# Quad_VCA_CTRL_v1.net
KiCad netlist of a schematic drawn in EAGLE
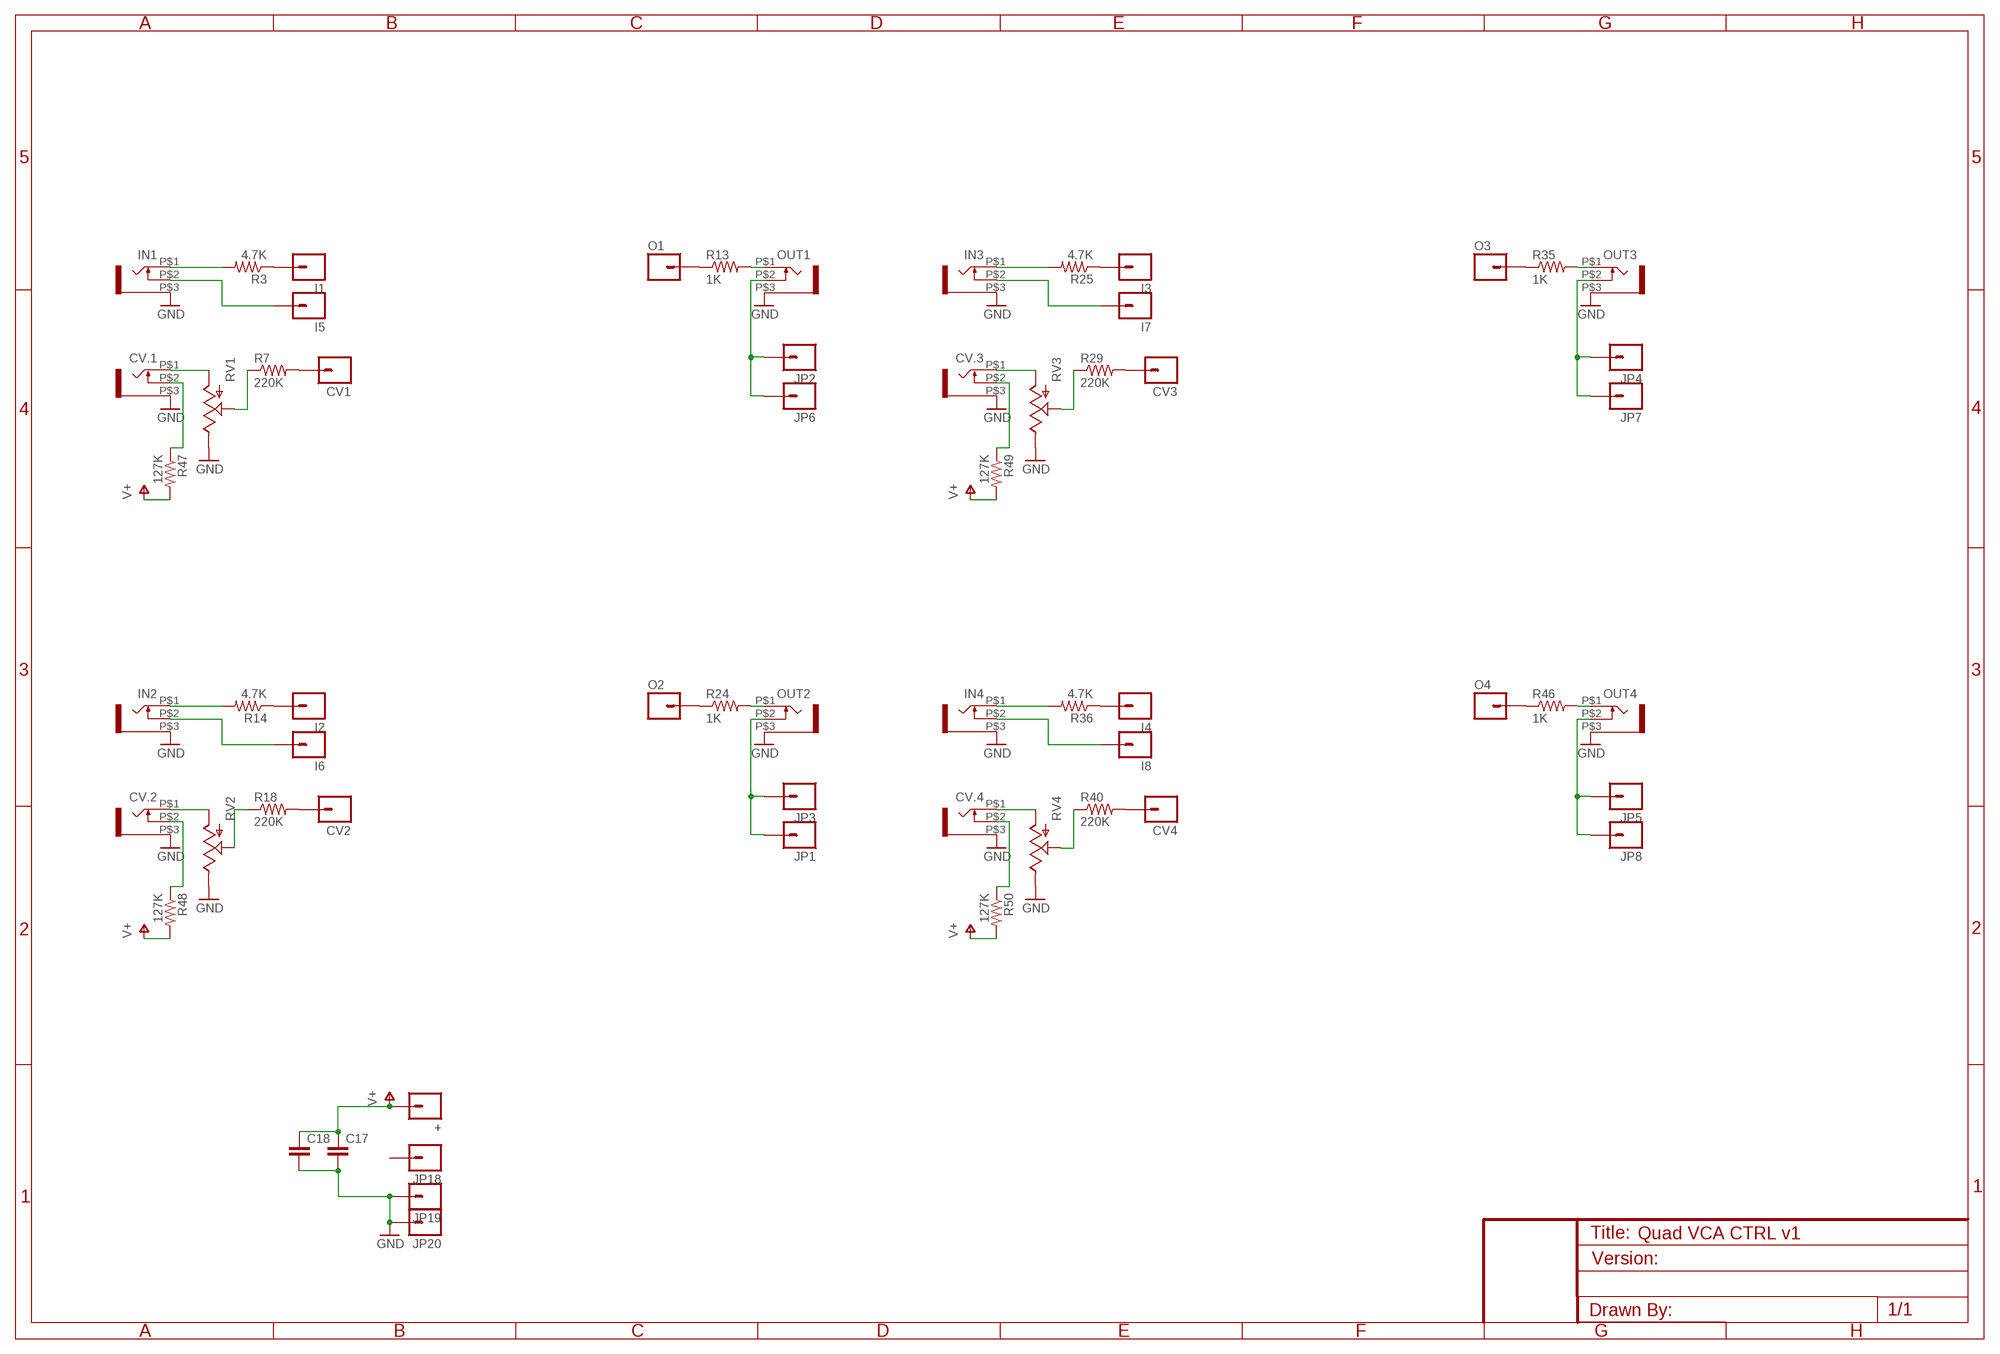
[diagram p0: schematic, sheet 1]

(export (version "E")
  (design (tool "Eeschema 10.0.6"))
  (components
    (comp (ref "+")
      (value "M01PTH")
      (footprint "eagle-import:1X01")
      (libsource (lib "eagle-import") (part "M01PTH"))
    )
    (comp (ref "C17")
      (value "CAP0805")
      (footprint "eagle-import:0805")
      (libsource (lib "eagle-import") (part "CAP0805"))
    )
    (comp (ref "C18")
      (value "CAP0805")
      (footprint "eagle-import:0805")
      (libsource (lib "eagle-import") (part "CAP0805"))
    )
    (comp (ref "CV.1")
      (value "WQP-PJ301M-12_JACK")
      (footprint "eagle-import:WQP-PJ301M-12_JACK")
      (libsource (lib "eagle-import") (part "WQP-PJ301M-12_JACK"))
    )
    (comp (ref "CV.2")
      (value "WQP-PJ301M-12_JACK")
      (footprint "eagle-import:WQP-PJ301M-12_JACK")
      (libsource (lib "eagle-import") (part "WQP-PJ301M-12_JACK"))
    )
    (comp (ref "CV.3")
      (value "WQP-PJ301M-12_JACK")
      (footprint "eagle-import:WQP-PJ301M-12_JACK")
      (libsource (lib "eagle-import") (part "WQP-PJ301M-12_JACK"))
    )
    (comp (ref "CV.4")
      (value "WQP-PJ301M-12_JACK")
      (footprint "eagle-import:WQP-PJ301M-12_JACK")
      (libsource (lib "eagle-import") (part "WQP-PJ301M-12_JACK"))
    )
    (comp (ref "CV1")
      (value "M01PTH")
      (footprint "eagle-import:1X01")
      (libsource (lib "eagle-import") (part "M01PTH"))
    )
    (comp (ref "CV2")
      (value "M01PTH")
      (footprint "eagle-import:1X01")
      (libsource (lib "eagle-import") (part "M01PTH"))
    )
    (comp (ref "CV3")
      (value "M01PTH")
      (footprint "eagle-import:1X01")
      (libsource (lib "eagle-import") (part "M01PTH"))
    )
    (comp (ref "CV4")
      (value "M01PTH")
      (footprint "eagle-import:1X01")
      (libsource (lib "eagle-import") (part "M01PTH"))
    )
    (comp (ref "I1")
      (value "M01PTH")
      (footprint "eagle-import:1X01")
      (libsource (lib "eagle-import") (part "M01PTH"))
    )
    (comp (ref "I2")
      (value "M01PTH")
      (footprint "eagle-import:1X01")
      (libsource (lib "eagle-import") (part "M01PTH"))
    )
    (comp (ref "I3")
      (value "M01PTH")
      (footprint "eagle-import:1X01")
      (libsource (lib "eagle-import") (part "M01PTH"))
    )
    (comp (ref "I4")
      (value "M01PTH")
      (footprint "eagle-import:1X01")
      (libsource (lib "eagle-import") (part "M01PTH"))
    )
    (comp (ref "I5")
      (value "M01PTH")
      (footprint "eagle-import:1X01")
      (libsource (lib "eagle-import") (part "M01PTH"))
    )
    (comp (ref "I6")
      (value "M01PTH")
      (footprint "eagle-import:1X01")
      (libsource (lib "eagle-import") (part "M01PTH"))
    )
    (comp (ref "I7")
      (value "M01PTH")
      (footprint "eagle-import:1X01")
      (libsource (lib "eagle-import") (part "M01PTH"))
    )
    (comp (ref "I8")
      (value "M01PTH")
      (footprint "eagle-import:1X01")
      (libsource (lib "eagle-import") (part "M01PTH"))
    )
    (comp (ref "IN1")
      (value "WQP-PJ301M-12_JACK")
      (footprint "eagle-import:WQP-PJ301M-12_JACK")
      (libsource (lib "eagle-import") (part "WQP-PJ301M-12_JACK"))
    )
    (comp (ref "IN2")
      (value "WQP-PJ301M-12_JACK")
      (footprint "eagle-import:WQP-PJ301M-12_JACK")
      (libsource (lib "eagle-import") (part "WQP-PJ301M-12_JACK"))
    )
    (comp (ref "IN3")
      (value "WQP-PJ301M-12_JACK")
      (footprint "eagle-import:WQP-PJ301M-12_JACK")
      (libsource (lib "eagle-import") (part "WQP-PJ301M-12_JACK"))
    )
    (comp (ref "IN4")
      (value "WQP-PJ301M-12_JACK")
      (footprint "eagle-import:WQP-PJ301M-12_JACK")
      (libsource (lib "eagle-import") (part "WQP-PJ301M-12_JACK"))
    )
    (comp (ref "JP1")
      (value "M01PTH")
      (footprint "eagle-import:1X01")
      (libsource (lib "eagle-import") (part "M01PTH"))
    )
    (comp (ref "JP2")
      (value "M01PTH")
      (footprint "eagle-import:1X01")
      (libsource (lib "eagle-import") (part "M01PTH"))
    )
    (comp (ref "JP3")
      (value "M01PTH")
      (footprint "eagle-import:1X01")
      (libsource (lib "eagle-import") (part "M01PTH"))
    )
    (comp (ref "JP4")
      (value "M01PTH")
      (footprint "eagle-import:1X01")
      (libsource (lib "eagle-import") (part "M01PTH"))
    )
    (comp (ref "JP5")
      (value "M01PTH")
      (footprint "eagle-import:1X01")
      (libsource (lib "eagle-import") (part "M01PTH"))
    )
    (comp (ref "JP6")
      (value "M01PTH")
      (footprint "eagle-import:1X01")
      (libsource (lib "eagle-import") (part "M01PTH"))
    )
    (comp (ref "JP7")
      (value "M01PTH")
      (footprint "eagle-import:1X01")
      (libsource (lib "eagle-import") (part "M01PTH"))
    )
    (comp (ref "JP8")
      (value "M01PTH")
      (footprint "eagle-import:1X01")
      (libsource (lib "eagle-import") (part "M01PTH"))
    )
    (comp (ref "JP18")
      (value "M01PTH")
      (footprint "eagle-import:1X01")
      (libsource (lib "eagle-import") (part "M01PTH"))
    )
    (comp (ref "JP19")
      (value "M01PTH")
      (footprint "eagle-import:1X01")
      (libsource (lib "eagle-import") (part "M01PTH"))
    )
    (comp (ref "JP20")
      (value "M01PTH")
      (footprint "eagle-import:1X01")
      (libsource (lib "eagle-import") (part "M01PTH"))
    )
    (comp (ref "O1")
      (value "M01PTH")
      (footprint "eagle-import:1X01")
      (libsource (lib "eagle-import") (part "M01PTH"))
    )
    (comp (ref "O2")
      (value "M01PTH")
      (footprint "eagle-import:1X01")
      (libsource (lib "eagle-import") (part "M01PTH"))
    )
    (comp (ref "O3")
      (value "M01PTH")
      (footprint "eagle-import:1X01")
      (libsource (lib "eagle-import") (part "M01PTH"))
    )
    (comp (ref "O4")
      (value "M01PTH")
      (footprint "eagle-import:1X01")
      (libsource (lib "eagle-import") (part "M01PTH"))
    )
    (comp (ref "OUT1")
      (value "WQP-PJ301M-12_JACK")
      (footprint "eagle-import:WQP-PJ301M-12_JACK")
      (libsource (lib "eagle-import") (part "WQP-PJ301M-12_JACK"))
    )
    (comp (ref "OUT2")
      (value "WQP-PJ301M-12_JACK")
      (footprint "eagle-import:WQP-PJ301M-12_JACK")
      (libsource (lib "eagle-import") (part "WQP-PJ301M-12_JACK"))
    )
    (comp (ref "OUT3")
      (value "WQP-PJ301M-12_JACK")
      (footprint "eagle-import:WQP-PJ301M-12_JACK")
      (libsource (lib "eagle-import") (part "WQP-PJ301M-12_JACK"))
    )
    (comp (ref "OUT4")
      (value "WQP-PJ301M-12_JACK")
      (footprint "eagle-import:WQP-PJ301M-12_JACK")
      (libsource (lib "eagle-import") (part "WQP-PJ301M-12_JACK"))
    )
    (comp (ref "R3")
      (value "4.7K")
      (footprint "eagle-import:0805")
      (libsource (lib "eagle-import") (part "RESISTOR0805-RES"))
    )
    (comp (ref "R7")
      (value "220K")
      (footprint "eagle-import:0805")
      (libsource (lib "eagle-import") (part "RESISTOR0805-RES"))
    )
    (comp (ref "R13")
      (value "1K")
      (footprint "eagle-import:0805")
      (libsource (lib "eagle-import") (part "RESISTOR0805-RES"))
    )
    (comp (ref "R14")
      (value "4.7K")
      (footprint "eagle-import:0805")
      (libsource (lib "eagle-import") (part "RESISTOR0805-RES"))
    )
    (comp (ref "R18")
      (value "220K")
      (footprint "eagle-import:0805")
      (libsource (lib "eagle-import") (part "RESISTOR0805-RES"))
    )
    (comp (ref "R24")
      (value "1K")
      (footprint "eagle-import:0805")
      (libsource (lib "eagle-import") (part "RESISTOR0805-RES"))
    )
    (comp (ref "R25")
      (value "4.7K")
      (footprint "eagle-import:0805")
      (libsource (lib "eagle-import") (part "RESISTOR0805-RES"))
    )
    (comp (ref "R29")
      (value "220K")
      (footprint "eagle-import:0805")
      (libsource (lib "eagle-import") (part "RESISTOR0805-RES"))
    )
    (comp (ref "R35")
      (value "1K")
      (footprint "eagle-import:0805")
      (libsource (lib "eagle-import") (part "RESISTOR0805-RES"))
    )
    (comp (ref "R36")
      (value "4.7K")
      (footprint "eagle-import:0805")
      (libsource (lib "eagle-import") (part "RESISTOR0805-RES"))
    )
    (comp (ref "R40")
      (value "220K")
      (footprint "eagle-import:0805")
      (libsource (lib "eagle-import") (part "RESISTOR0805-RES"))
    )
    (comp (ref "R46")
      (value "1K")
      (footprint "eagle-import:0805")
      (libsource (lib "eagle-import") (part "RESISTOR0805-RES"))
    )
    (comp (ref "R47")
      (value "127K")
      (footprint "eagle-import:0805")
      (libsource (lib "eagle-import") (part "RESISTOR0805-RES"))
    )
    (comp (ref "R48")
      (value "127K")
      (footprint "eagle-import:0805")
      (libsource (lib "eagle-import") (part "RESISTOR0805-RES"))
    )
    (comp (ref "R49")
      (value "127K")
      (footprint "eagle-import:0805")
      (libsource (lib "eagle-import") (part "RESISTOR0805-RES"))
    )
    (comp (ref "R50")
      (value "127K")
      (footprint "eagle-import:0805")
      (libsource (lib "eagle-import") (part "RESISTOR0805-RES"))
    )
    (comp (ref "RV1")
      (value "POT")
      (footprint "eagle-import:ALPS_POT")
      (libsource (lib "eagle-import") (part "POT"))
    )
    (comp (ref "RV2")
      (value "POT")
      (footprint "eagle-import:ALPS_POT")
      (libsource (lib "eagle-import") (part "POT"))
    )
    (comp (ref "RV3")
      (value "POT")
      (footprint "eagle-import:ALPS_POT")
      (libsource (lib "eagle-import") (part "POT"))
    )
    (comp (ref "RV4")
      (value "POT")
      (footprint "eagle-import:ALPS_POT")
      (libsource (lib "eagle-import") (part "POT"))
    )
  )
  (nets
    (net (code "1") (name "GND") (class "Default")
      (node (ref "C17") (pin "2") (pinfunction "2_2") (pintype "passive"))
      (node (ref "C18") (pin "2") (pinfunction "2_2") (pintype "passive"))
      (node (ref "CV.1") (pin "P$3") (pinfunction "1_P$3") (pintype "passive"))
      (node (ref "CV.2") (pin "P$3") (pinfunction "1_P$3") (pintype "passive"))
      (node (ref "CV.3") (pin "P$3") (pinfunction "1_P$3") (pintype "passive"))
      (node (ref "CV.4") (pin "P$3") (pinfunction "1_P$3") (pintype "passive"))
      (node (ref "IN1") (pin "P$3") (pinfunction "1_P$3") (pintype "passive"))
      (node (ref "IN2") (pin "P$3") (pinfunction "1_P$3") (pintype "passive"))
      (node (ref "IN3") (pin "P$3") (pinfunction "1_P$3") (pintype "passive"))
      (node (ref "IN4") (pin "P$3") (pinfunction "1_P$3") (pintype "passive"))
      (node (ref "JP19") (pin "1") (pinfunction "1_1") (pintype "passive"))
      (node (ref "JP20") (pin "1") (pinfunction "1_1") (pintype "passive"))
      (node (ref "OUT1") (pin "P$3") (pinfunction "1_P$3") (pintype "passive"))
      (node (ref "OUT2") (pin "P$3") (pinfunction "1_P$3") (pintype "passive"))
      (node (ref "OUT3") (pin "P$3") (pinfunction "1_P$3") (pintype "passive"))
      (node (ref "OUT4") (pin "P$3") (pinfunction "1_P$3") (pintype "passive"))
      (node (ref "RV1") (pin "P$1") (pinfunction "E_P$1") (pintype "passive"))
      (node (ref "RV2") (pin "P$1") (pinfunction "E_P$1") (pintype "passive"))
      (node (ref "RV3") (pin "P$1") (pinfunction "E_P$1") (pintype "passive"))
      (node (ref "RV4") (pin "P$1") (pinfunction "E_P$1") (pintype "passive"))
    )
    (net (code "2") (name "Net-(CV.1-2)") (class "Default")
      (node (ref "CV.1") (pin "P$1") (pinfunction "2_P$1") (pintype "passive"))
      (node (ref "RV1") (pin "P$3") (pinfunction "A_P$3") (pintype "passive"))
    )
    (net (code "3") (name "Net-(CV.1-3)") (class "Default")
      (node (ref "CV.1") (pin "P$2") (pinfunction "3_P$2") (pintype "passive"))
      (node (ref "R47") (pin "1") (pinfunction "1_1") (pintype "passive"))
    )
    (net (code "4") (name "Net-(CV.2-2)") (class "Default")
      (node (ref "CV.2") (pin "P$1") (pinfunction "2_P$1") (pintype "passive"))
      (node (ref "RV2") (pin "P$3") (pinfunction "A_P$3") (pintype "passive"))
    )
    (net (code "5") (name "Net-(CV.2-3)") (class "Default")
      (node (ref "CV.2") (pin "P$2") (pinfunction "3_P$2") (pintype "passive"))
      (node (ref "R48") (pin "1") (pinfunction "1_1") (pintype "passive"))
    )
    (net (code "6") (name "Net-(CV.3-2)") (class "Default")
      (node (ref "CV.3") (pin "P$1") (pinfunction "2_P$1") (pintype "passive"))
      (node (ref "RV3") (pin "P$3") (pinfunction "A_P$3") (pintype "passive"))
    )
    (net (code "7") (name "Net-(CV.3-3)") (class "Default")
      (node (ref "CV.3") (pin "P$2") (pinfunction "3_P$2") (pintype "passive"))
      (node (ref "R49") (pin "1") (pinfunction "1_1") (pintype "passive"))
    )
    (net (code "8") (name "Net-(CV.4-2)") (class "Default")
      (node (ref "CV.4") (pin "P$1") (pinfunction "2_P$1") (pintype "passive"))
      (node (ref "RV4") (pin "P$3") (pinfunction "A_P$3") (pintype "passive"))
    )
    (net (code "9") (name "Net-(CV.4-3)") (class "Default")
      (node (ref "CV.4") (pin "P$2") (pinfunction "3_P$2") (pintype "passive"))
      (node (ref "R50") (pin "1") (pinfunction "1_1") (pintype "passive"))
    )
    (net (code "10") (name "Net-(CV1-Pad1)") (class "Default")
      (node (ref "CV1") (pin "1") (pinfunction "1_1") (pintype "passive"))
      (node (ref "R7") (pin "2") (pinfunction "2_2") (pintype "passive"))
    )
    (net (code "11") (name "Net-(CV2-Pad1)") (class "Default")
      (node (ref "CV2") (pin "1") (pinfunction "1_1") (pintype "passive"))
      (node (ref "R18") (pin "2") (pinfunction "2_2") (pintype "passive"))
    )
    (net (code "12") (name "Net-(CV3-Pad1)") (class "Default")
      (node (ref "CV3") (pin "1") (pinfunction "1_1") (pintype "passive"))
      (node (ref "R29") (pin "2") (pinfunction "2_2") (pintype "passive"))
    )
    (net (code "13") (name "Net-(CV4-Pad1)") (class "Default")
      (node (ref "CV4") (pin "1") (pinfunction "1_1") (pintype "passive"))
      (node (ref "R40") (pin "2") (pinfunction "2_2") (pintype "passive"))
    )
    (net (code "14") (name "Net-(I1-Pad1)") (class "Default")
      (node (ref "I1") (pin "1") (pinfunction "1_1") (pintype "passive"))
      (node (ref "R3") (pin "1") (pinfunction "1_1") (pintype "passive"))
    )
    (net (code "15") (name "Net-(I2-Pad1)") (class "Default")
      (node (ref "I2") (pin "1") (pinfunction "1_1") (pintype "passive"))
      (node (ref "R14") (pin "1") (pinfunction "1_1") (pintype "passive"))
    )
    (net (code "16") (name "Net-(I3-Pad1)") (class "Default")
      (node (ref "I3") (pin "1") (pinfunction "1_1") (pintype "passive"))
      (node (ref "R25") (pin "1") (pinfunction "1_1") (pintype "passive"))
    )
    (net (code "17") (name "Net-(I4-Pad1)") (class "Default")
      (node (ref "I4") (pin "1") (pinfunction "1_1") (pintype "passive"))
      (node (ref "R36") (pin "1") (pinfunction "1_1") (pintype "passive"))
    )
    (net (code "18") (name "Net-(IN1-2)") (class "Default")
      (node (ref "IN1") (pin "P$1") (pinfunction "2_P$1") (pintype "passive"))
      (node (ref "R3") (pin "2") (pinfunction "2_2") (pintype "passive"))
    )
    (net (code "19") (name "Net-(IN1-3)") (class "Default")
      (node (ref "I5") (pin "1") (pinfunction "1_1") (pintype "passive"))
      (node (ref "IN1") (pin "P$2") (pinfunction "3_P$2") (pintype "passive"))
    )
    (net (code "20") (name "Net-(IN2-2)") (class "Default")
      (node (ref "IN2") (pin "P$1") (pinfunction "2_P$1") (pintype "passive"))
      (node (ref "R14") (pin "2") (pinfunction "2_2") (pintype "passive"))
    )
    (net (code "21") (name "Net-(IN2-3)") (class "Default")
      (node (ref "I6") (pin "1") (pinfunction "1_1") (pintype "passive"))
      (node (ref "IN2") (pin "P$2") (pinfunction "3_P$2") (pintype "passive"))
    )
    (net (code "22") (name "Net-(IN3-2)") (class "Default")
      (node (ref "IN3") (pin "P$1") (pinfunction "2_P$1") (pintype "passive"))
      (node (ref "R25") (pin "2") (pinfunction "2_2") (pintype "passive"))
    )
    (net (code "23") (name "Net-(IN3-3)") (class "Default")
      (node (ref "I7") (pin "1") (pinfunction "1_1") (pintype "passive"))
      (node (ref "IN3") (pin "P$2") (pinfunction "3_P$2") (pintype "passive"))
    )
    (net (code "24") (name "Net-(IN4-2)") (class "Default")
      (node (ref "IN4") (pin "P$1") (pinfunction "2_P$1") (pintype "passive"))
      (node (ref "R36") (pin "2") (pinfunction "2_2") (pintype "passive"))
    )
    (net (code "25") (name "Net-(IN4-3)") (class "Default")
      (node (ref "I8") (pin "1") (pinfunction "1_1") (pintype "passive"))
      (node (ref "IN4") (pin "P$2") (pinfunction "3_P$2") (pintype "passive"))
    )
    (net (code "26") (name "Net-(O1-Pad1)") (class "Default")
      (node (ref "O1") (pin "1") (pinfunction "1_1") (pintype "passive"))
      (node (ref "R13") (pin "1") (pinfunction "1_1") (pintype "passive"))
    )
    (net (code "27") (name "Net-(O2-Pad1)") (class "Default")
      (node (ref "O2") (pin "1") (pinfunction "1_1") (pintype "passive"))
      (node (ref "R24") (pin "1") (pinfunction "1_1") (pintype "passive"))
    )
    (net (code "28") (name "Net-(O3-Pad1)") (class "Default")
      (node (ref "O3") (pin "1") (pinfunction "1_1") (pintype "passive"))
      (node (ref "R35") (pin "1") (pinfunction "1_1") (pintype "passive"))
    )
    (net (code "29") (name "Net-(O4-Pad1)") (class "Default")
      (node (ref "O4") (pin "1") (pinfunction "1_1") (pintype "passive"))
      (node (ref "R46") (pin "1") (pinfunction "1_1") (pintype "passive"))
    )
    (net (code "30") (name "Net-(OUT1-2)") (class "Default")
      (node (ref "OUT1") (pin "P$1") (pinfunction "2_P$1") (pintype "passive"))
      (node (ref "R13") (pin "2") (pinfunction "2_2") (pintype "passive"))
    )
    (net (code "31") (name "Net-(OUT1-3)") (class "Default")
      (node (ref "JP2") (pin "1") (pinfunction "1_1") (pintype "passive"))
      (node (ref "JP6") (pin "1") (pinfunction "1_1") (pintype "passive"))
      (node (ref "OUT1") (pin "P$2") (pinfunction "3_P$2") (pintype "passive"))
    )
    (net (code "32") (name "Net-(OUT2-2)") (class "Default")
      (node (ref "OUT2") (pin "P$1") (pinfunction "2_P$1") (pintype "passive"))
      (node (ref "R24") (pin "2") (pinfunction "2_2") (pintype "passive"))
    )
    (net (code "33") (name "Net-(OUT2-3)") (class "Default")
      (node (ref "JP1") (pin "1") (pinfunction "1_1") (pintype "passive"))
      (node (ref "JP3") (pin "1") (pinfunction "1_1") (pintype "passive"))
      (node (ref "OUT2") (pin "P$2") (pinfunction "3_P$2") (pintype "passive"))
    )
    (net (code "34") (name "Net-(OUT3-2)") (class "Default")
      (node (ref "OUT3") (pin "P$1") (pinfunction "2_P$1") (pintype "passive"))
      (node (ref "R35") (pin "2") (pinfunction "2_2") (pintype "passive"))
    )
    (net (code "35") (name "Net-(OUT3-3)") (class "Default")
      (node (ref "JP4") (pin "1") (pinfunction "1_1") (pintype "passive"))
      (node (ref "JP7") (pin "1") (pinfunction "1_1") (pintype "passive"))
      (node (ref "OUT3") (pin "P$2") (pinfunction "3_P$2") (pintype "passive"))
    )
    (net (code "36") (name "Net-(OUT4-2)") (class "Default")
      (node (ref "OUT4") (pin "P$1") (pinfunction "2_P$1") (pintype "passive"))
      (node (ref "R46") (pin "2") (pinfunction "2_2") (pintype "passive"))
    )
    (net (code "37") (name "Net-(OUT4-3)") (class "Default")
      (node (ref "JP5") (pin "1") (pinfunction "1_1") (pintype "passive"))
      (node (ref "JP8") (pin "1") (pinfunction "1_1") (pintype "passive"))
      (node (ref "OUT4") (pin "P$2") (pinfunction "3_P$2") (pintype "passive"))
    )
    (net (code "38") (name "Net-(RV1-S)") (class "Default")
      (node (ref "R7") (pin "1") (pinfunction "1_1") (pintype "passive"))
      (node (ref "RV1") (pin "P$2") (pinfunction "S_P$2") (pintype "passive"))
    )
    (net (code "39") (name "Net-(RV2-S)") (class "Default")
      (node (ref "R18") (pin "1") (pinfunction "1_1") (pintype "passive"))
      (node (ref "RV2") (pin "P$2") (pinfunction "S_P$2") (pintype "passive"))
    )
    (net (code "40") (name "Net-(RV3-S)") (class "Default")
      (node (ref "R29") (pin "1") (pinfunction "1_1") (pintype "passive"))
      (node (ref "RV3") (pin "P$2") (pinfunction "S_P$2") (pintype "passive"))
    )
    (net (code "41") (name "Net-(RV4-S)") (class "Default")
      (node (ref "R40") (pin "1") (pinfunction "1_1") (pintype "passive"))
      (node (ref "RV4") (pin "P$2") (pinfunction "S_P$2") (pintype "passive"))
    )
    (net (code "42") (name "V+") (class "Default")
      (node (ref "+") (pin "1") (pinfunction "1_1") (pintype "passive"))
      (node (ref "C17") (pin "1") (pinfunction "1_1") (pintype "passive"))
      (node (ref "C18") (pin "1") (pinfunction "1_1") (pintype "passive"))
      (node (ref "R47") (pin "2") (pinfunction "2_2") (pintype "passive"))
      (node (ref "R48") (pin "2") (pinfunction "2_2") (pintype "passive"))
      (node (ref "R49") (pin "2") (pinfunction "2_2") (pintype "passive"))
      (node (ref "R50") (pin "2") (pinfunction "2_2") (pintype "passive"))
    )
    (net (code "43") (name "unconnected-(JP18-Pad1)") (class "Default")
      (node (ref "JP18") (pin "1") (pinfunction "1_1") (pintype "passive"))
    )
  )
)
